# board6.net
KiCad netlist of a schematic drawn in Altium Designer
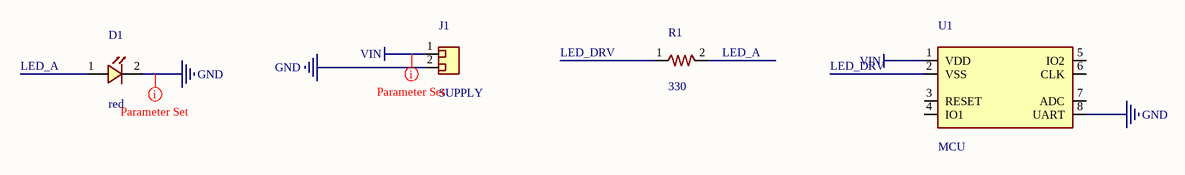
[diagram p0: board6.SchDoc]

(export (version "E")
  (design (tool "Eeschema 10.0.6"))
  (components
    (comp (ref "D1")
      (value "red")
      (footprint "board6:LED0603_Kingbright_APT1608SURCK")
      (libsource (lib "board6") (part "LED"))
    )
    (comp (ref "J1")
      (value "SUPPLY")
      (footprint "board6:Header_1x2_P2.54")
      (libsource (lib "board6") (part "Connector_2"))
    )
    (comp (ref "R1")
      (value "330")
      (footprint "board6:Chip_0603")
      (libsource (lib "board6") (part "Resistor"))
    )
    (comp (ref "U1")
      (value "MCU")
      (footprint "board6:DIP8_Microchip_P")
      (libsource (lib "board6") (part "Microcontroller"))
    )
  )
  (nets
    (net (code "1") (name "/LED_A") (class "Default")
      (node (ref "D1") (pin "1") (pinfunction "A_1") (pintype "passive"))
      (node (ref "R1") (pin "2") (pinfunction "B_2") (pintype "passive"))
    )
    (net (code "2") (name "/LED_DRV") (class "Default")
      (node (ref "R1") (pin "1") (pinfunction "A_1") (pintype "passive"))
      (node (ref "U1") (pin "2") (pinfunction "VSS_2") (pintype "passive"))
    )
    (net (code "3") (name "GND") (class "Default")
      (node (ref "D1") (pin "2") (pinfunction "K_2") (pintype "passive"))
      (node (ref "J1") (pin "2") (pinfunction "Passive_2") (pintype "passive"))
      (node (ref "U1") (pin "8") (pinfunction "UART_8") (pintype "passive"))
    )
    (net (code "4") (name "VIN") (class "Default")
      (node (ref "J1") (pin "1") (pinfunction "Passive_1") (pintype "passive"))
      (node (ref "U1") (pin "1") (pinfunction "VDD_1") (pintype "passive"))
    )
    (net (code "5") (name "unconnected-(U1-ADC-Pad7)") (class "Default")
      (node (ref "U1") (pin "7") (pinfunction "ADC_7") (pintype "passive"))
    )
    (net (code "6") (name "unconnected-(U1-CLK-Pad6)") (class "Default")
      (node (ref "U1") (pin "6") (pinfunction "CLK_6") (pintype "passive"))
    )
    (net (code "7") (name "unconnected-(U1-IO1-Pad4)") (class "Default")
      (node (ref "U1") (pin "4") (pinfunction "IO1_4") (pintype "passive"))
    )
    (net (code "8") (name "unconnected-(U1-IO2-Pad5)") (class "Default")
      (node (ref "U1") (pin "5") (pinfunction "IO2_5") (pintype "passive"))
    )
    (net (code "9") (name "unconnected-(U1-RESET-Pad3)") (class "Default")
      (node (ref "U1") (pin "3") (pinfunction "RESET_3") (pintype "passive"))
    )
  )
)
